# Power_Path.net
KiCad netlist of a schematic drawn in Altium Designer
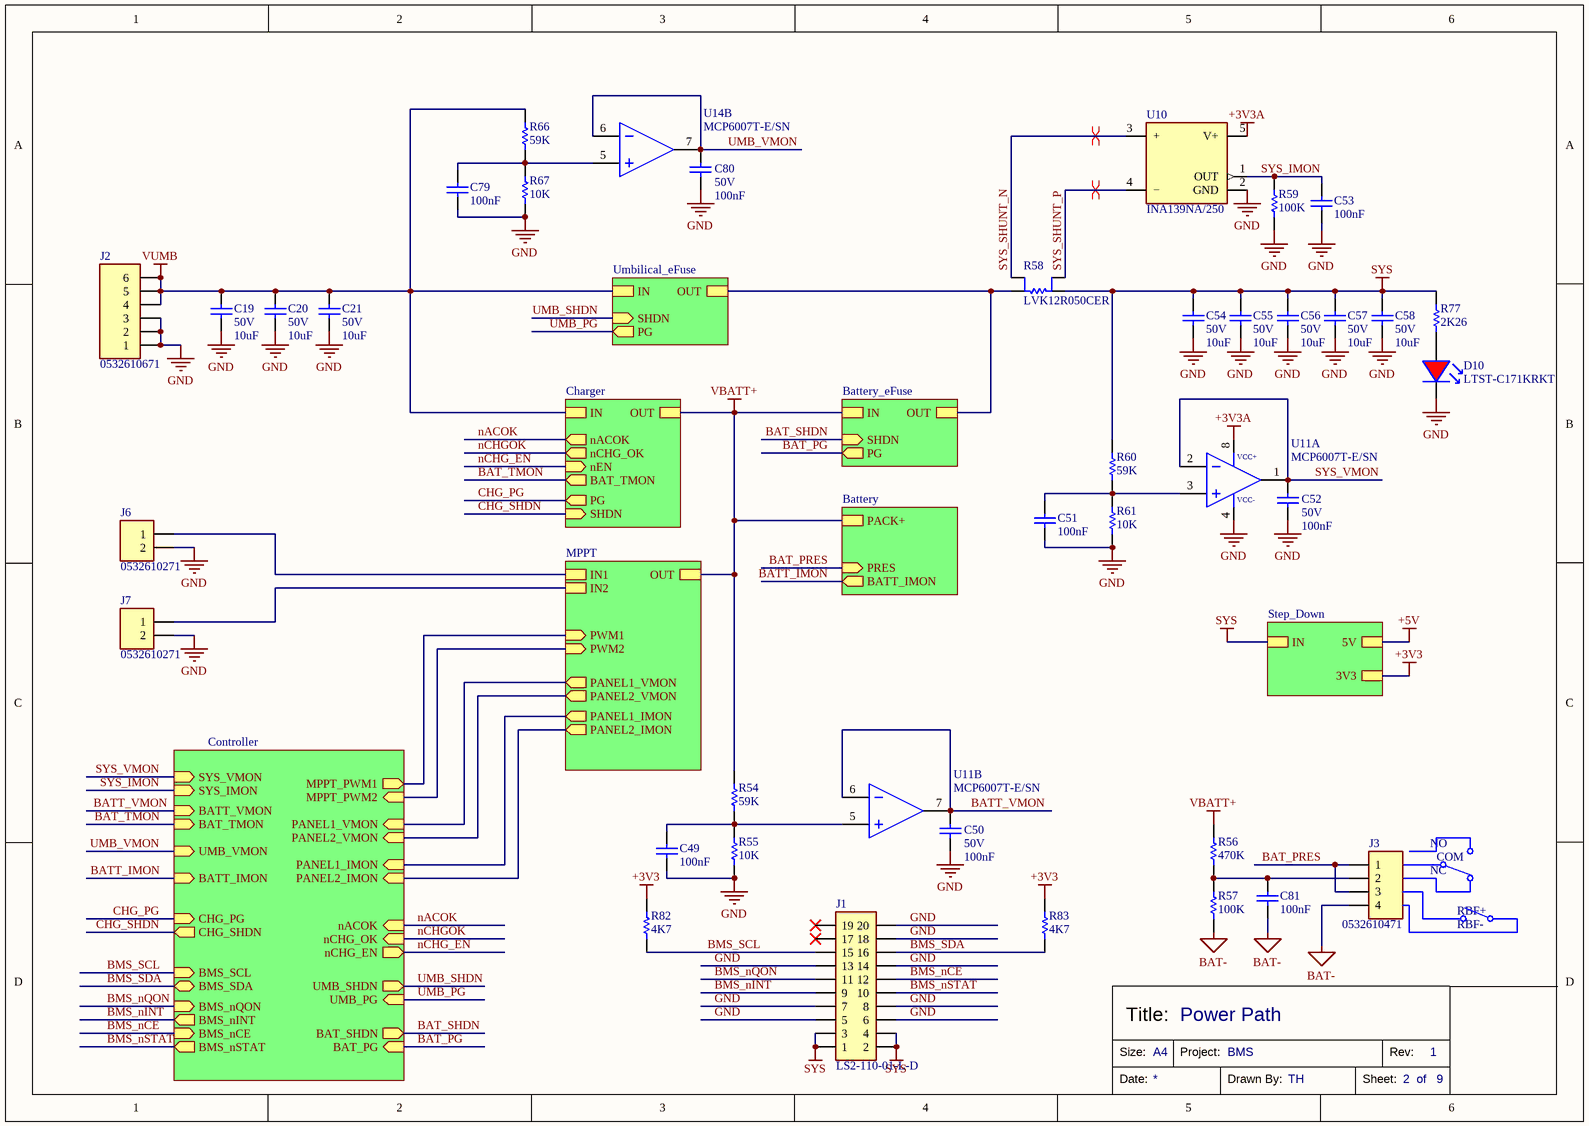
[diagram p0: Power_Path.SchDoc]

(export (version "E")
  (design (tool "Eeschema 10.0.6"))
  (components
    (comp (ref "C19")
      (value "CL32B106KBJNNNE")
      (footprint "CAPC1210X090")
      (description "10 µF ±10% 50V Ceramic Capacitor X7R 1210 (3225 Metric)")
      (fields
        (field (name "DISTRIBUTOR PART NUMBER") "1276-3387-1-ND")
        (field (name "TOLERANCE") "10%")
        (field (name "VOLTAGE RATING") "50V")
        (field (name "CAPACITANCE") "10uF")
      )
      (libsource (lib "Ahristi_Library") (part "CL32B106KBJNNNE"))
    )
    (comp (ref "C20")
      (value "CL32B106KBJNNNE")
      (footprint "CAPC1210X090")
      (description "10 µF ±10% 50V Ceramic Capacitor X7R 1210 (3225 Metric)")
      (fields
        (field (name "DISTRIBUTOR PART NUMBER") "1276-3387-1-ND")
        (field (name "TOLERANCE") "10%")
        (field (name "VOLTAGE RATING") "50V")
        (field (name "CAPACITANCE") "10uF")
      )
      (libsource (lib "Ahristi_Library") (part "CL32B106KBJNNNE"))
    )
    (comp (ref "C21")
      (value "CL32B106KBJNNNE")
      (footprint "CAPC1210X090")
      (description "10 µF ±10% 50V Ceramic Capacitor X7R 1210 (3225 Metric)")
      (fields
        (field (name "DISTRIBUTOR PART NUMBER") "1276-3387-1-ND")
        (field (name "TOLERANCE") "10%")
        (field (name "VOLTAGE RATING") "50V")
        (field (name "CAPACITANCE") "10uF")
      )
      (libsource (lib "Ahristi_Library") (part "CL32B106KBJNNNE"))
    )
    (comp (ref "C49")
      (value "C0603C104K5RACTU")
      (footprint "CAPC0603X040")
      (description "0.1 µF ±10% 50V Ceramic Capacitor X7R 0603 (1608 Metric)")
      (fields
        (field (name "DISTRIBUTOR PART NUMBER") "399-C0603C104K5RACTUCT-ND")
        (field (name "TOLERANCE") "10%")
        (field (name "CAPACITANCE") "100nF")
      )
      (libsource (lib "Ahristi_Library") (part "C0603C104K5RACTU"))
    )
    (comp (ref "C50")
      (value "C0603C104K5RACTU")
      (footprint "CAPC0603X040")
      (description "0.1 µF ±10% 50V Ceramic Capacitor X7R 0603 (1608 Metric)")
      (fields
        (field (name "DISTRIBUTOR PART NUMBER") "399-C0603C104K5RACTUCT-ND")
        (field (name "TOLERANCE") "10%")
        (field (name "VOLTAGE RATING") "50V")
        (field (name "CAPACITANCE") "100nF")
      )
      (libsource (lib "Ahristi_Library") (part "C0603C104K5RACTU"))
    )
    (comp (ref "C51")
      (value "C0603C104K5RACTU")
      (footprint "CAPC0603X040")
      (description "0.1 µF ±10% 50V Ceramic Capacitor X7R 0603 (1608 Metric)")
      (fields
        (field (name "DISTRIBUTOR PART NUMBER") "399-C0603C104K5RACTUCT-ND")
        (field (name "TOLERANCE") "10%")
        (field (name "CAPACITANCE") "100nF")
      )
      (libsource (lib "Ahristi_Library") (part "C0603C104K5RACTU"))
    )
    (comp (ref "C52")
      (value "C0603C104K5RACTU")
      (footprint "CAPC0603X040")
      (description "0.1 µF ±10% 50V Ceramic Capacitor X7R 0603 (1608 Metric)")
      (fields
        (field (name "DISTRIBUTOR PART NUMBER") "399-C0603C104K5RACTUCT-ND")
        (field (name "TOLERANCE") "10%")
        (field (name "VOLTAGE RATING") "50V")
        (field (name "CAPACITANCE") "100nF")
      )
      (libsource (lib "Ahristi_Library") (part "C0603C104K5RACTU"))
    )
    (comp (ref "C53")
      (value "C0603C104K5RACTU")
      (footprint "CAPC0603X040")
      (description "0.1 µF ±10% 50V Ceramic Capacitor X7R 0603 (1608 Metric)")
      (fields
        (field (name "DISTRIBUTOR PART NUMBER") "399-C0603C104K5RACTUCT-ND")
        (field (name "TOLERANCE") "10%")
        (field (name "CAPACITANCE") "100nF")
      )
      (libsource (lib "Ahristi_Library") (part "C0603C104K5RACTU"))
    )
    (comp (ref "C54")
      (value "CL32B106KBJNNNE")
      (footprint "CAPC1210X090")
      (description "10 µF ±10% 50V Ceramic Capacitor X7R 1210 (3225 Metric)")
      (fields
        (field (name "DISTRIBUTOR PART NUMBER") "1276-3387-1-ND")
        (field (name "TOLERANCE") "10%")
        (field (name "VOLTAGE RATING") "50V")
        (field (name "CAPACITANCE") "10uF")
      )
      (libsource (lib "Ahristi_Library") (part "CL32B106KBJNNNE"))
    )
    (comp (ref "C55")
      (value "CL32B106KBJNNNE")
      (footprint "CAPC1210X090")
      (description "10 µF ±10% 50V Ceramic Capacitor X7R 1210 (3225 Metric)")
      (fields
        (field (name "DISTRIBUTOR PART NUMBER") "1276-3387-1-ND")
        (field (name "TOLERANCE") "10%")
        (field (name "VOLTAGE RATING") "50V")
        (field (name "CAPACITANCE") "10uF")
      )
      (libsource (lib "Ahristi_Library") (part "CL32B106KBJNNNE"))
    )
    (comp (ref "C56")
      (value "CL32B106KBJNNNE")
      (footprint "CAPC1210X090")
      (description "10 µF ±10% 50V Ceramic Capacitor X7R 1210 (3225 Metric)")
      (fields
        (field (name "DISTRIBUTOR PART NUMBER") "1276-3387-1-ND")
        (field (name "TOLERANCE") "10%")
        (field (name "VOLTAGE RATING") "50V")
        (field (name "CAPACITANCE") "10uF")
      )
      (libsource (lib "Ahristi_Library") (part "CL32B106KBJNNNE"))
    )
    (comp (ref "C57")
      (value "CL32B106KBJNNNE")
      (footprint "CAPC1210X090")
      (description "10 µF ±10% 50V Ceramic Capacitor X7R 1210 (3225 Metric)")
      (fields
        (field (name "DISTRIBUTOR PART NUMBER") "1276-3387-1-ND")
        (field (name "TOLERANCE") "10%")
        (field (name "VOLTAGE RATING") "50V")
        (field (name "CAPACITANCE") "10uF")
      )
      (libsource (lib "Ahristi_Library") (part "CL32B106KBJNNNE"))
    )
    (comp (ref "C58")
      (value "CL32B106KBJNNNE")
      (footprint "CAPC1210X090")
      (description "10 µF ±10% 50V Ceramic Capacitor X7R 1210 (3225 Metric)")
      (fields
        (field (name "DISTRIBUTOR PART NUMBER") "1276-3387-1-ND")
        (field (name "TOLERANCE") "10%")
        (field (name "VOLTAGE RATING") "50V")
        (field (name "CAPACITANCE") "10uF")
      )
      (libsource (lib "Ahristi_Library") (part "CL32B106KBJNNNE"))
    )
    (comp (ref "C79")
      (value "C0603C104K5RACTU")
      (footprint "CAPC0603X040")
      (description "0.1 µF ±10% 50V Ceramic Capacitor X7R 0603 (1608 Metric)")
      (fields
        (field (name "DISTRIBUTOR PART NUMBER") "399-C0603C104K5RACTUCT-ND")
        (field (name "TOLERANCE") "10%")
        (field (name "CAPACITANCE") "100nF")
      )
      (libsource (lib "Ahristi_Library") (part "C0603C104K5RACTU"))
    )
    (comp (ref "C80")
      (value "C0603C104K5RACTU")
      (footprint "CAPC0603X040")
      (description "0.1 µF ±10% 50V Ceramic Capacitor X7R 0603 (1608 Metric)")
      (fields
        (field (name "DISTRIBUTOR PART NUMBER") "399-C0603C104K5RACTUCT-ND")
        (field (name "TOLERANCE") "10%")
        (field (name "VOLTAGE RATING") "50V")
        (field (name "CAPACITANCE") "100nF")
      )
      (libsource (lib "Ahristi_Library") (part "C0603C104K5RACTU"))
    )
    (comp (ref "C81")
      (value "C0603C104K5RACTU")
      (footprint "CAPC0603X040")
      (description "0.1 µF ±10% 50V Ceramic Capacitor X7R 0603 (1608 Metric)")
      (fields
        (field (name "DISTRIBUTOR PART NUMBER") "399-C0603C104K5RACTUCT-ND")
        (field (name "TOLERANCE") "10%")
        (field (name "CAPACITANCE") "100nF")
      )
      (libsource (lib "Ahristi_Library") (part "C0603C104K5RACTU"))
    )
    (comp (ref "D10")
      (value "LTST-C171KRKT")
      (footprint "LEDR_0805")
      (description "Red 631nm LED Indication - Discrete 2V 0805 (2012 Metric)")
      (fields (field (name "DISTRIBUTOR PART NUMBER") "160-1427-1-ND"))
      (libsource (lib "Ahristi_Library") (part "LTST-C171KRKT"))
    )
    (comp (ref "J1")
      (value "LS2-110-01-L-D")
      (footprint "LS2-110-01-L-D")
      (description "Connector Self Mating 20 Position , Non-Gendered, Hermaphroditic Through Hole Gold")
      (fields (field (name "DISTRIBUTOR PART NUMBER") "SAM9665-ND"))
      (libsource (lib "Ahristi_Library") (part "LS2-110-01-L-D"))
    )
    (comp (ref "J2")
      (value "0532610671")
      (footprint "0532610671")
      (description "Connector Header Surface Mount, Right Angle 6 position 0.049\" (1.25mm) Picoblade")
      (fields (field (name "DISTRIBUTOR PART NUMBER") "WM7624CT-ND"))
      (libsource (lib "Ahristi_Library") (part "0532610671"))
    )
    (comp (ref "J3")
      (value "0532610471")
      (footprint "0532610471")
      (description "Connector Header Surface Mount, Right Angle 4 position 0.049\" (1.25mm) Molex Picoblade")
      (fields (field (name "DISTRIBUTOR PART NUMBER") "WM7622CT-ND"))
      (libsource (lib "Ahristi_Library") (part "0532610471"))
    )
    (comp (ref "J6")
      (value "0532610271")
      (footprint "0532610271")
      (description "Connector Header, Picoblade Surface Mount, Right Angle 2 position 0.049\" (1.25mm)")
      (fields (field (name "DISTRIBUTOR PART NUMBER") "WM7620CT-ND"))
      (libsource (lib "Ahristi_Library") (part "0532610271"))
    )
    (comp (ref "J7")
      (value "0532610271")
      (footprint "0532610271")
      (description "Connector Header, Picoblade Surface Mount, Right Angle 2 position 0.049\" (1.25mm)")
      (fields (field (name "DISTRIBUTOR PART NUMBER") "WM7620CT-ND"))
      (libsource (lib "Ahristi_Library") (part "0532610271"))
    )
    (comp (ref "R54")
      (value "RMCF0603FT59K0")
      (footprint "RESC0603")
      (description "59 kOhms ±1% 0.1W, 1/10W Chip Resistor 0603 (1608 Metric) Automotive AEC-Q200 Thick Film")
      (fields
        (field (name "TOLERANCE") "1%")
        (field (name "DISTRIBUTOR PART NUMBER") "RMCF0603FT59K0CT-ND")
        (field (name "RESISTANCE") "59K")
      )
      (libsource (lib "Ahristi_Library") (part "RMCF0603FT59K0"))
    )
    (comp (ref "R55")
      (value "RMCF0603FT10K0")
      (footprint "RESC0603")
      (description "10 kOhms ±1% 0.1W, 1/10W Chip Resistor 0603 (1608 Metric) Automotive AEC-Q200 Thick Film")
      (fields
        (field (name "TOLERANCE") "1%")
        (field (name "DISTRIBUTOR PART NUMBER") "RMCF0603FT10K0CT-ND")
        (field (name "RESISTANCE") "10K")
      )
      (libsource (lib "Ahristi_Library") (part "RMCF0603FT10K0"))
    )
    (comp (ref "R56")
      (value "RMCF0603FT470K")
      (footprint "RESC0603")
      (description "470 kOhms ±1% 0.1W, 1/10W Chip Resistor 0603 (1608 Metric) Automotive AEC-Q200 Thick Film")
      (fields
        (field (name "TOLERANCE") "1%")
        (field (name "DISTRIBUTOR PART NUMBER") "RMCF0603FT470KCT-ND")
        (field (name "RESISTANCE") "470K")
      )
      (libsource (lib "Ahristi_Library") (part "RMCF0603FT470K"))
    )
    (comp (ref "R57")
      (value "RMCF0603FT100K")
      (footprint "RESC0603")
      (description "100 kOhms ±1% 0.1W, 1/10W Chip Resistor 0603 (1608 Metric) Automotive AEC-Q200 Thick Film")
      (fields
        (field (name "TOLERANCE") "1%")
        (field (name "DISTRIBUTOR PART NUMBER") "RMCF0603FT100KCT-ND")
        (field (name "RESISTANCE") "100K")
      )
      (libsource (lib "Ahristi_Library") (part "RMCF0603FT100K"))
    )
    (comp (ref "R58")
      (value "LVK12R050CER")
      (footprint "LVK12R050CER-1")
      (description "Resistor, Current Sense 50 mOhms ±0.25% 0.5W, Moisture Resistant Thick Film")
      (fields
        (field (name "DISTRIBUTOR PART NUMBER") "588-LVK12R050CER")
        (field (name "MANUFACTURER") "Ohmite")
      )
      (libsource (lib "Ahristi_Library") (part "LVK12R050CER"))
    )
    (comp (ref "R59")
      (value "RMCF0603FT100K")
      (footprint "RESC0603")
      (description "100 kOhms ±1% 0.1W, 1/10W Chip Resistor 0603 (1608 Metric) Automotive AEC-Q200 Thick Film")
      (fields
        (field (name "TOLERANCE") "1%")
        (field (name "DISTRIBUTOR PART NUMBER") "RMCF0603FT100KCT-ND")
        (field (name "RESISTANCE") "100K")
      )
      (libsource (lib "Ahristi_Library") (part "RMCF0603FT100K"))
    )
    (comp (ref "R60")
      (value "RMCF0603FT59K0")
      (footprint "RESC0603")
      (description "59 kOhms ±1% 0.1W, 1/10W Chip Resistor 0603 (1608 Metric) Automotive AEC-Q200 Thick Film")
      (fields
        (field (name "TOLERANCE") "1%")
        (field (name "DISTRIBUTOR PART NUMBER") "RMCF0603FT59K0CT-ND")
        (field (name "RESISTANCE") "59K")
      )
      (libsource (lib "Ahristi_Library") (part "RMCF0603FT59K0"))
    )
    (comp (ref "R61")
      (value "RMCF0603FT10K0")
      (footprint "RESC0603")
      (description "10 kOhms ±1% 0.1W, 1/10W Chip Resistor 0603 (1608 Metric) Automotive AEC-Q200 Thick Film")
      (fields
        (field (name "TOLERANCE") "1%")
        (field (name "DISTRIBUTOR PART NUMBER") "RMCF0603FT10K0CT-ND")
        (field (name "RESISTANCE") "10K")
      )
      (libsource (lib "Ahristi_Library") (part "RMCF0603FT10K0"))
    )
    (comp (ref "R66")
      (value "RMCF0603FT59K0")
      (footprint "RESC0603")
      (description "59 kOhms ±1% 0.1W, 1/10W Chip Resistor 0603 (1608 Metric) Automotive AEC-Q200 Thick Film")
      (fields
        (field (name "TOLERANCE") "1%")
        (field (name "DISTRIBUTOR PART NUMBER") "RMCF0603FT59K0CT-ND")
        (field (name "RESISTANCE") "59K")
      )
      (libsource (lib "Ahristi_Library") (part "RMCF0603FT59K0"))
    )
    (comp (ref "R67")
      (value "RMCF0603FT10K0")
      (footprint "RESC0603")
      (description "10 kOhms ±1% 0.1W, 1/10W Chip Resistor 0603 (1608 Metric) Automotive AEC-Q200 Thick Film")
      (fields
        (field (name "TOLERANCE") "1%")
        (field (name "DISTRIBUTOR PART NUMBER") "RMCF0603FT10K0CT-ND")
        (field (name "RESISTANCE") "10K")
      )
      (libsource (lib "Ahristi_Library") (part "RMCF0603FT10K0"))
    )
    (comp (ref "R77")
      (value "RMCF0603FT2K26")
      (footprint "RESC0603")
      (description "2.26 kOhms ±1% 0.1W, 1/10W Chip Resistor 0603 (1608 Metric) Automotive AEC-Q200 Thick Film")
      (fields
        (field (name "TOLERANCE") "1%")
        (field (name "DISTRIBUTOR PART NUMBER") "RMCF0603FT2K26CT-ND")
        (field (name "RESISTANCE") "2K26")
      )
      (libsource (lib "Ahristi_Library") (part "RMCF0603FT2K26"))
    )
    (comp (ref "R82")
      (value "RMCF0603FT4K7")
      (footprint "RESC0603")
      (description "4.7 kOhms ±1% 0.1W, 1/10W Chip Resistor 0603 (1608 Metric) Automotive AEC-Q200 Thick Film")
      (fields
        (field (name "TOLERANCE") "1%")
        (field (name "DISTRIBUTOR PART NUMBER") "RMCF0603FT4K70CT-ND")
        (field (name "RESISTANCE") "4K7")
      )
      (libsource (lib "Ahristi_Library") (part "RMCF0603FT4K7"))
    )
    (comp (ref "R83")
      (value "RMCF0603FT4K7")
      (footprint "RESC0603")
      (description "4.7 kOhms ±1% 0.1W, 1/10W Chip Resistor 0603 (1608 Metric) Automotive AEC-Q200 Thick Film")
      (fields
        (field (name "TOLERANCE") "1%")
        (field (name "DISTRIBUTOR PART NUMBER") "RMCF0603FT4K70CT-ND")
        (field (name "RESISTANCE") "4K7")
      )
      (libsource (lib "Ahristi_Library") (part "RMCF0603FT4K7"))
    )
    (comp (ref "U10")
      (value "INA139NA/250")
      (footprint "SOT23-5 IC")
      (description "40V Current Sense Amplifier 1 Circuit 8-MSOP")
      (fields (field (name "DISTRIBUTOR PART NUMBER") "INA139NA/250CT-ND"))
      (libsource (lib "Ahristi_Library") (part "INA139NA/250"))
    )
    (comp (ref "U11")
      (value "MCP6007T-E/SN")
      (footprint "SOIC-8")
      (description "Operational Amplifier general purpose, 2-Circuit 1.8V ~ 5.5V 1MHz")
      (fields (field (name "DISTRIBUTOR PART NUMBER") "150-MCP6007T-E/SNCT-ND"))
      (libsource (lib "Ahristi_Library") (part "MCP6007T-E/SN"))
    )
    (comp (ref "U14")
      (value "MCP6007T-E/SN")
      (footprint "SOIC-8")
      (description "Operational Amplifier general purpose, 2-Circuit 1.8V ~ 5.5V 1MHz")
      (fields (field (name "DISTRIBUTOR PART NUMBER") "150-MCP6007T-E/SNCT-ND"))
      (libsource (lib "Ahristi_Library") (part "MCP6007T-E/SN"))
    )
  )
  (nets
    (net (code "1") (name "+3V3") (class "Default")
      (node (ref "R82") (pin "2") (pinfunction "2_2") (pintype "passive"))
      (node (ref "R83") (pin "2") (pinfunction "2_2") (pintype "passive"))
    )
    (net (code "2") (name "+3V3A") (class "Default")
      (node (ref "U10") (pin "5") (pinfunction "V+_5") (pintype "passive"))
      (node (ref "U11") (pin "8") (pinfunction "VCC+_8") (pintype "passive"))
    )
    (net (code "5") (name "/BATT_VMON") (class "Default")
      (node (ref "C50") (pin "2") (pinfunction "2_2") (pintype "passive"))
      (node (ref "U11") (pin "6") (pinfunction "INB-_6") (pintype "passive"))
      (node (ref "U11") (pin "7") (pinfunction "OUTB_7") (pintype "passive"))
    )
    (net (code "7") (name "/BAT_PRES") (class "Default")
      (node (ref "J3") (pin "1") (pinfunction "1_1") (pintype "passive"))
      (node (ref "J3") (pin "3") (pinfunction "3_3") (pintype "passive"))
    )
    (net (code "10") (name "/BMS_SCL") (class "Default")
      (node (ref "J1") (pin "15") (pinfunction "15_15") (pintype "passive"))
      (node (ref "R82") (pin "1") (pinfunction "1_1") (pintype "passive"))
    )
    (net (code "11") (name "/BMS_SDA") (class "Default")
      (node (ref "J1") (pin "16") (pinfunction "16_16") (pintype "passive"))
      (node (ref "R83") (pin "1") (pinfunction "1_1") (pintype "passive"))
    )
    (net (code "12") (name "/BMS_nCE") (class "Default")
      (node (ref "J1") (pin "12") (pinfunction "12_12") (pintype "passive"))
    )
    (net (code "13") (name "/BMS_nINT") (class "Default")
      (node (ref "J1") (pin "9") (pinfunction "9_9") (pintype "passive"))
    )
    (net (code "14") (name "/BMS_nQON") (class "Default")
      (node (ref "J1") (pin "11") (pinfunction "11_11") (pintype "passive"))
    )
    (net (code "15") (name "/BMS_nSTAT") (class "Default")
      (node (ref "J1") (pin "10") (pinfunction "10_10") (pintype "passive"))
    )
    (net (code "18") (name "/IN1") (class "Default")
      (node (ref "J6") (pin "1") (pinfunction "1_1") (pintype "passive"))
    )
    (net (code "19") (name "/IN2") (class "Default")
      (node (ref "J7") (pin "1") (pinfunction "1_1") (pintype "passive"))
    )
    (net (code "22") (name "/OUT") (class "Default")
      (node (ref "R58") (pin "1") (pinfunction "1_1") (pintype "passive"))
    )
    (net (code "27") (name "/SYS_IMON") (class "Default")
      (node (ref "C53") (pin "2") (pinfunction "2_2") (pintype "passive"))
      (node (ref "R59") (pin "2") (pinfunction "2_2") (pintype "passive"))
      (node (ref "U10") (pin "1") (pinfunction "OUT_1") (pintype "output"))
    )
    (net (code "28") (name "/SYS_SHUNT_N") (class "Default")
      (node (ref "R58") (pin "2") (pinfunction "2_2") (pintype "passive"))
      (node (ref "U10") (pin "3") (pinfunction "+_3") (pintype "passive"))
    )
    (net (code "29") (name "/SYS_SHUNT_P") (class "Default")
      (node (ref "R58") (pin "3") (pinfunction "3_3") (pintype "passive"))
      (node (ref "U10") (pin "4") (pinfunction "−_4") (pintype "passive"))
    )
    (net (code "30") (name "/SYS_VMON") (class "Default")
      (node (ref "C52") (pin "2") (pinfunction "2_2") (pintype "passive"))
      (node (ref "U11") (pin "1") (pinfunction "OUTA_1") (pintype "passive"))
      (node (ref "U11") (pin "2") (pinfunction "INA-_2") (pintype "passive"))
    )
    (net (code "33") (name "/UMB_VMON") (class "Default")
      (node (ref "C80") (pin "2") (pinfunction "2_2") (pintype "passive"))
      (node (ref "U14") (pin "6") (pinfunction "INB-_6") (pintype "passive"))
      (node (ref "U14") (pin "7") (pinfunction "OUTB_7") (pintype "passive"))
    )
    (net (code "37") (name "BAT-") (class "Default")
      (node (ref "C81") (pin "1") (pinfunction "1_1") (pintype "passive"))
      (node (ref "J3") (pin "4") (pinfunction "4_4") (pintype "passive"))
      (node (ref "R57") (pin "1") (pinfunction "1_1") (pintype "passive"))
    )
    (net (code "38") (name "GND") (class "Default")
      (node (ref "C19") (pin "1") (pinfunction "1_1") (pintype "passive"))
      (node (ref "C20") (pin "1") (pinfunction "1_1") (pintype "passive"))
      (node (ref "C21") (pin "1") (pinfunction "1_1") (pintype "passive"))
      (node (ref "C49") (pin "1") (pinfunction "1_1") (pintype "passive"))
      (node (ref "C50") (pin "1") (pinfunction "1_1") (pintype "passive"))
      (node (ref "C51") (pin "1") (pinfunction "1_1") (pintype "passive"))
      (node (ref "C52") (pin "1") (pinfunction "1_1") (pintype "passive"))
      (node (ref "C53") (pin "1") (pinfunction "1_1") (pintype "passive"))
      (node (ref "C54") (pin "1") (pinfunction "1_1") (pintype "passive"))
      (node (ref "C55") (pin "1") (pinfunction "1_1") (pintype "passive"))
      (node (ref "C56") (pin "1") (pinfunction "1_1") (pintype "passive"))
      (node (ref "C57") (pin "1") (pinfunction "1_1") (pintype "passive"))
      (node (ref "C58") (pin "1") (pinfunction "1_1") (pintype "passive"))
      (node (ref "C79") (pin "1") (pinfunction "1_1") (pintype "passive"))
      (node (ref "C80") (pin "1") (pinfunction "1_1") (pintype "passive"))
      (node (ref "D10") (pin "K") (pinfunction "K_K") (pintype "passive"))
      (node (ref "J1") (pin "13") (pinfunction "13_13") (pintype "passive"))
      (node (ref "J1") (pin "14") (pinfunction "14_14") (pintype "passive"))
      (node (ref "J1") (pin "18") (pinfunction "18_18") (pintype "passive"))
      (node (ref "J1") (pin "20") (pinfunction "20_20") (pintype "passive"))
      (node (ref "J1") (pin "5") (pinfunction "5_5") (pintype "passive"))
      (node (ref "J1") (pin "6") (pinfunction "6_6") (pintype "passive"))
      (node (ref "J1") (pin "7") (pinfunction "7_7") (pintype "passive"))
      (node (ref "J1") (pin "8") (pinfunction "8_8") (pintype "passive"))
      (node (ref "J2") (pin "1") (pinfunction "1_1") (pintype "passive"))
      (node (ref "J2") (pin "2") (pinfunction "2_2") (pintype "passive"))
      (node (ref "J2") (pin "3") (pinfunction "3_3") (pintype "passive"))
      (node (ref "J6") (pin "2") (pinfunction "2_2") (pintype "passive"))
      (node (ref "J7") (pin "2") (pinfunction "2_2") (pintype "passive"))
      (node (ref "R55") (pin "1") (pinfunction "1_1") (pintype "passive"))
      (node (ref "R59") (pin "1") (pinfunction "1_1") (pintype "passive"))
      (node (ref "R61") (pin "1") (pinfunction "1_1") (pintype "passive"))
      (node (ref "R67") (pin "1") (pinfunction "1_1") (pintype "passive"))
      (node (ref "U10") (pin "2") (pinfunction "GND_2") (pintype "passive"))
      (node (ref "U11") (pin "4") (pinfunction "VCC-_4") (pintype "passive"))
    )
    (net (code "39") (name "Net-(C81-Pad2)") (class "Default")
      (node (ref "C81") (pin "2") (pinfunction "2_2") (pintype "passive"))
      (node (ref "J3") (pin "2") (pinfunction "2_2") (pintype "passive"))
      (node (ref "R56") (pin "1") (pinfunction "1_1") (pintype "passive"))
      (node (ref "R57") (pin "2") (pinfunction "2_2") (pintype "passive"))
    )
    (net (code "40") (name "Net-(D10-PadA)") (class "Default")
      (node (ref "D10") (pin "A") (pinfunction "A_A") (pintype "passive"))
      (node (ref "R77") (pin "1") (pinfunction "1_1") (pintype "passive"))
    )
    (net (code "41") (name "Net-(U11A-INA+)") (class "Default")
      (node (ref "C51") (pin "2") (pinfunction "2_2") (pintype "passive"))
      (node (ref "R60") (pin "1") (pinfunction "1_1") (pintype "passive"))
      (node (ref "R61") (pin "2") (pinfunction "2_2") (pintype "passive"))
      (node (ref "U11") (pin "3") (pinfunction "INA+_3") (pintype "passive"))
    )
    (net (code "42") (name "Net-(U11B-INB+)") (class "Default")
      (node (ref "C49") (pin "2") (pinfunction "2_2") (pintype "passive"))
      (node (ref "R54") (pin "1") (pinfunction "1_1") (pintype "passive"))
      (node (ref "R55") (pin "2") (pinfunction "2_2") (pintype "passive"))
      (node (ref "U11") (pin "5") (pinfunction "INB+_5") (pintype "passive"))
    )
    (net (code "43") (name "Net-(U14B-INB+)") (class "Default")
      (node (ref "C79") (pin "2") (pinfunction "2_2") (pintype "passive"))
      (node (ref "R66") (pin "1") (pinfunction "1_1") (pintype "passive"))
      (node (ref "R67") (pin "2") (pinfunction "2_2") (pintype "passive"))
      (node (ref "U14") (pin "5") (pinfunction "INB+_5") (pintype "passive"))
    )
    (net (code "44") (name "SYS") (class "Default")
      (node (ref "C54") (pin "2") (pinfunction "2_2") (pintype "passive"))
      (node (ref "C55") (pin "2") (pinfunction "2_2") (pintype "passive"))
      (node (ref "C56") (pin "2") (pinfunction "2_2") (pintype "passive"))
      (node (ref "C57") (pin "2") (pinfunction "2_2") (pintype "passive"))
      (node (ref "C58") (pin "2") (pinfunction "2_2") (pintype "passive"))
      (node (ref "J1") (pin "1") (pinfunction "1_1") (pintype "passive"))
      (node (ref "J1") (pin "2") (pinfunction "2_2") (pintype "passive"))
      (node (ref "J1") (pin "3") (pinfunction "3_3") (pintype "passive"))
      (node (ref "J1") (pin "4") (pinfunction "4_4") (pintype "passive"))
      (node (ref "R58") (pin "4") (pinfunction "4_4") (pintype "passive"))
      (node (ref "R60") (pin "2") (pinfunction "2_2") (pintype "passive"))
      (node (ref "R77") (pin "2") (pinfunction "2_2") (pintype "passive"))
    )
    (net (code "45") (name "VBATT+") (class "Default")
      (node (ref "R54") (pin "2") (pinfunction "2_2") (pintype "passive"))
      (node (ref "R56") (pin "2") (pinfunction "2_2") (pintype "passive"))
    )
    (net (code "46") (name "VUMB") (class "Default")
      (node (ref "C19") (pin "2") (pinfunction "2_2") (pintype "passive"))
      (node (ref "C20") (pin "2") (pinfunction "2_2") (pintype "passive"))
      (node (ref "C21") (pin "2") (pinfunction "2_2") (pintype "passive"))
      (node (ref "J2") (pin "4") (pinfunction "4_4") (pintype "passive"))
      (node (ref "J2") (pin "5") (pinfunction "5_5") (pintype "passive"))
      (node (ref "J2") (pin "6") (pinfunction "6_6") (pintype "passive"))
      (node (ref "R66") (pin "2") (pinfunction "2_2") (pintype "passive"))
    )
    (net (code "47") (name "unconnected-(J1-Pad17)") (class "Default")
      (node (ref "J1") (pin "17") (pinfunction "17_17") (pintype "passive+no_connect"))
    )
    (net (code "48") (name "unconnected-(J1-Pad19)") (class "Default")
      (node (ref "J1") (pin "19") (pinfunction "19_19") (pintype "passive+no_connect"))
    )
  )
)
